# MCU.net
KiCad netlist of a schematic drawn in Altium Designer
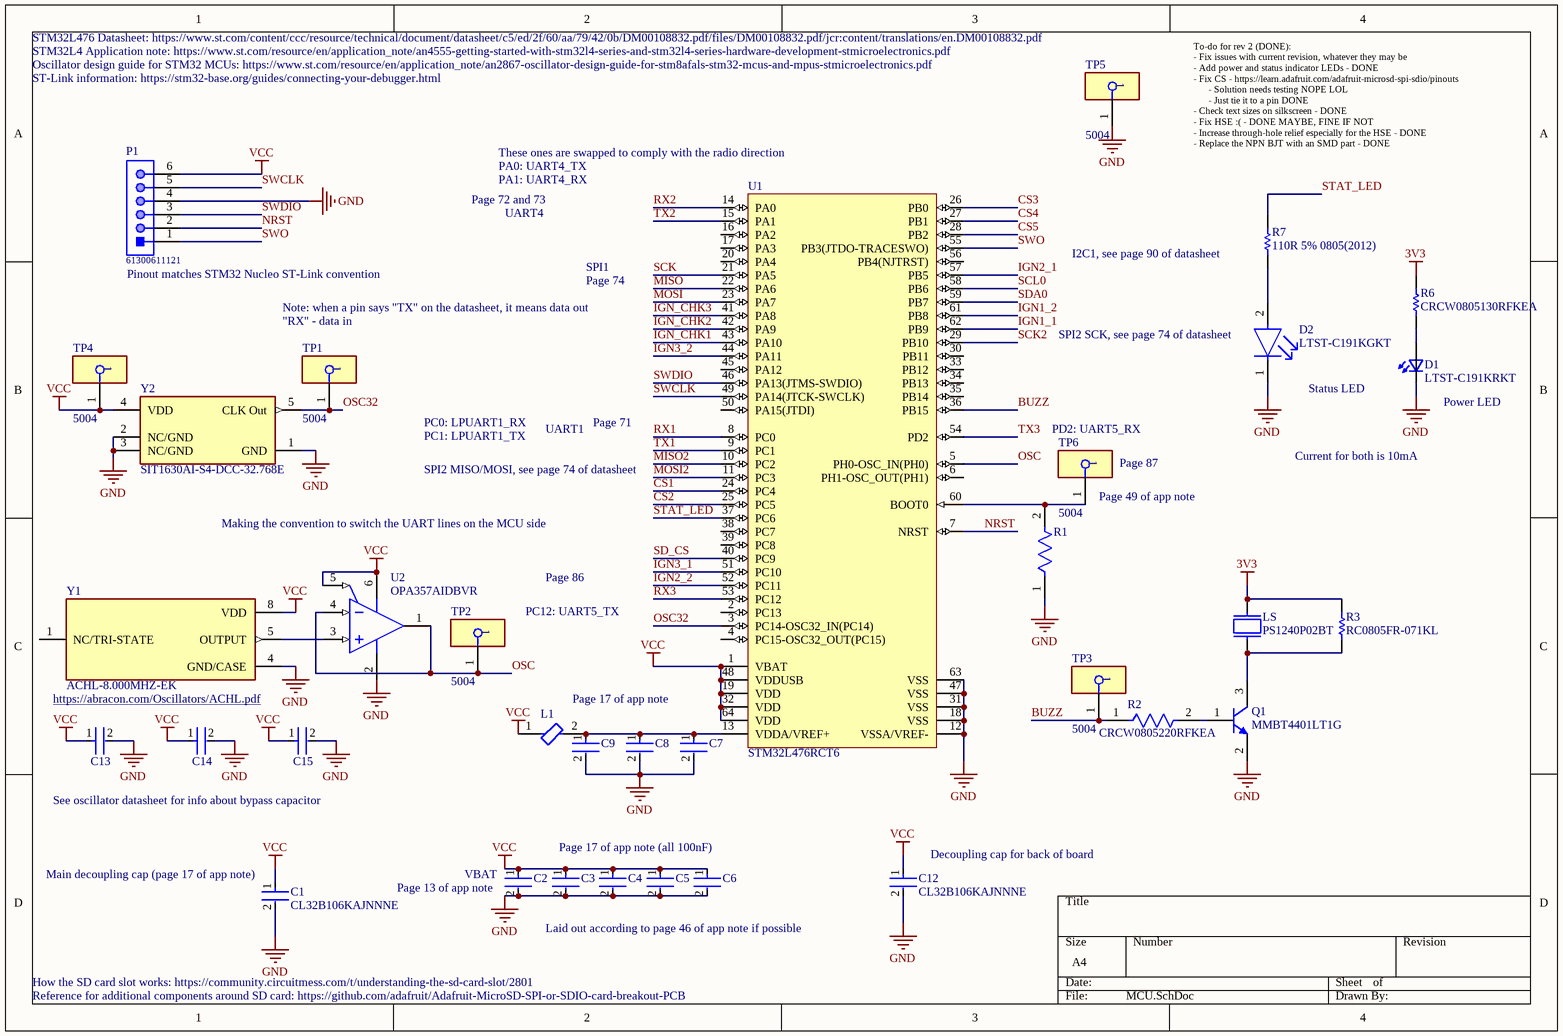
[diagram p0: MCU.SchDoc]

(export (version "E")
  (design (tool "Eeschema 10.0.6"))
  (components
    (comp (ref "C1")
      (value "CL32B106KAJNNNE")
      (footprint "FP-CL32-IPC_B")
      (description "Cap Ceramic 10uF 25V X7R ±10% SMD 1210 +125°C Embossed T/R")
      (fields (field (name "TOLERANCE") "10%") (field (name "VOLTAGE") "25V"))
      (libsource (lib "Altium Content Vault") (part "b4654b650e69147ec39a6b967a45e02"))
    )
    (comp (ref "C2")
      (value "CC0603KRX7R9BB104")
      (footprint "FP-CC0603-DA-MFG")
      (description "CAP CER 0.1UF 50V X7R 0603")
      (fields (field (name "MANUFACTURER") "YAGEO") (field (name "VOLTAGE") "50 V"))
      (libsource (lib "Altium Content Vault") (part "11868f565c42a9108669ba33697ecf6"))
    )
    (comp (ref "C3")
      (value "CC0603KRX7R9BB104")
      (footprint "FP-CC0603-DA-MFG")
      (description "CAP CER 0.1UF 50V X7R 0603")
      (fields (field (name "MANUFACTURER") "YAGEO") (field (name "VOLTAGE") "50 V"))
      (libsource (lib "Altium Content Vault") (part "11868f565c42a9108669ba33697ecf6"))
    )
    (comp (ref "C4")
      (value "CC0603KRX7R9BB104")
      (footprint "FP-CC0603-DA-MFG")
      (description "CAP CER 0.1UF 50V X7R 0603")
      (fields (field (name "MANUFACTURER") "YAGEO") (field (name "VOLTAGE") "50 V"))
      (libsource (lib "Altium Content Vault") (part "11868f565c42a9108669ba33697ecf6"))
    )
    (comp (ref "C5")
      (value "CC0603KRX7R9BB104")
      (footprint "FP-CC0603-DA-MFG")
      (description "CAP CER 0.1UF 50V X7R 0603")
      (fields (field (name "MANUFACTURER") "YAGEO") (field (name "VOLTAGE") "50 V"))
      (libsource (lib "Altium Content Vault") (part "11868f565c42a9108669ba33697ecf6"))
    )
    (comp (ref "C6")
      (value "CC0603KRX7R9BB104")
      (footprint "FP-CC0603-DA-MFG")
      (description "CAP CER 0.1UF 50V X7R 0603")
      (fields (field (name "MANUFACTURER") "YAGEO") (field (name "VOLTAGE") "50 V"))
      (libsource (lib "Altium Content Vault") (part "11868f565c42a9108669ba33697ecf6"))
    )
    (comp (ref "C7")
      (value "CC0603KRX7R9BB104")
      (footprint "FP-CC0603-DA-MFG")
      (description "CAP CER 0.1UF 50V X7R 0603")
      (fields (field (name "MANUFACTURER") "YAGEO") (field (name "VOLTAGE") "50 V"))
      (libsource (lib "Altium Content Vault") (part "11868f565c42a9108669ba33697ecf6"))
    )
    (comp (ref "C8")
      (value "CC0603KRX7R9BB103")
      (footprint "FP-CC0603-DA-MFG")
      (description "CAP CER 10000PF 50V X7R 0603")
      (fields (field (name "TOLERANCE") "0.1") (field (name "MANUFACTURER") "YAGEO"))
      (libsource (lib "Altium Content Vault") (part "11868f565c42a9108669ba33697ecf6"))
    )
    (comp (ref "C9")
      (value "CL10A105KO8NNNC")
      (footprint "FP-CL10-IPC_A")
      (description "Cap Ceramic 1uF 16V X5R ±10% Pad SMD 0603 +85°C T/R")
      (fields (field (name "TOLERANCE") "10%") (field (name "VOLTAGE") "16V"))
      (libsource (lib "Altium Content Vault") (part "b4654b650e69147ec39a6b967a45e02"))
    )
    (comp (ref "C12")
      (value "CL32B106KAJNNNE")
      (footprint "FP-CL32-IPC_B")
      (description "Cap Ceramic 10uF 25V X7R ±10% SMD 1210 +125°C Embossed T/R")
      (fields (field (name "TOLERANCE") "10%") (field (name "VOLTAGE") "25V"))
      (libsource (lib "Altium Content Vault") (part "b4654b650e69147ec39a6b967a45e02"))
    )
    (comp (ref "C13")
      (value "CC0603KRX7R9BB103")
      (footprint "FP-CC0603-DA-MFG")
      (description "CAP CER 10000PF 50V X7R 0603")
      (fields (field (name "TOLERANCE") "0.1") (field (name "MANUFACTURER") "YAGEO"))
      (libsource (lib "Altium Content Vault") (part "11868f565c42a9108669ba33697ecf6"))
    )
    (comp (ref "C14")
      (value "CC0603KRX7R9BB103")
      (footprint "FP-CC0603-DA-MFG")
      (description "CAP CER 10000PF 50V X7R 0603")
      (fields (field (name "TOLERANCE") "0.1") (field (name "MANUFACTURER") "YAGEO"))
      (libsource (lib "Altium Content Vault") (part "11868f565c42a9108669ba33697ecf6"))
    )
    (comp (ref "C15")
      (value "CL10A105KO8NNNC")
      (footprint "FP-CL10-IPC_A")
      (description "Cap Ceramic 1uF 16V X5R ±10% Pad SMD 0603 +85°C T/R")
      (fields (field (name "TOLERANCE") "10%") (field (name "VOLTAGE") "16V"))
      (libsource (lib "Altium Content Vault") (part "b4654b650e69147ec39a6b967a45e02"))
    )
    (comp (ref "D1")
      (value "LTST-C191KRKT")
      (footprint "0603")
      (description "http://octopart.com/ltst-c190krkt-lite-on-549893")
      (fields (field (name "LCSC PART #") "C125099"))
      (libsource (lib "LTST-C191KRKT") (part "LTST-C191KRKT"))
    )
    (comp (ref "D2")
      (value "LTST-C191KGKT")
      (footprint "FP-LTST-C191KGKT-MFG")
      (description "LED GREEN CLEAR SMD")
      (fields (field (name "LCSC PART #") "C125098"))
      (libsource (lib "Altium Content Vault") (part "8706943c75ba83719d021d2fdc84c58"))
    )
    (comp (ref "L1")
      (value "BLM18EG601SN1D")
      (footprint "FP-BLM18-0_15-t0_8-MFG")
      (description "Chip Ferrite Bead, 0603, 600Ω @ 100MHz, 0.35Ω, 25%, 500mA")
      (fields (field (name "TOLERANCE") "25%") (field (name "LCSC PART #") "C20345"))
      (libsource (lib "Altium Content Vault") (part "5f30dd21d616792df468990f7003faa"))
    )
    (comp (ref "LS")
      (value "PS1240P02BT")
      (footprint "XDCR_PS1240P02BT")
      (description "Buzzers Transducer, Externally Driven Piezo 3V 4kHz 60dB @ 3V, 10cm Through Hole PC Pins")
      (fields (field (name "MF") "TDK"))
      (libsource (lib "PS1240P02BT") (part "PS1240P02BT"))
    )
    (comp (ref "P1")
      (value "61300611121")
      (footprint "61300611121")
      (description "THT Vertical Pin Header WR-PHD, Pitch 2.54 mm, Single Row, 6 pins")
      (fields (field (name "MANUFACTURER") "Wurth Elektronik") (field (name "PUBLISHER") "WurthElektronik"))
      (libsource (lib "Altium Content Vault") (part "WE-CN-1P-M-R6"))
    )
    (comp (ref "Q1")
      (value "MMBT4401LT1G")
      (footprint "ONSC-SOT-23-3-318-08_V")
      (description "Switching Transistor, NPN Silicon, 3-Pin SOT-23, Pb-Free, Tape and Reel")
      (fields (field (name "MANUFACTURER") "On Semiconductor") (field (name "LCSC PART #") "C31776"))
      (libsource (lib "Altium Content Vault") (part "ONSC-NPN-B1E2C3-3"))
    )
    (comp (ref "R1")
      (value "AC0805FR-0710KL")
      (footprint "FP-AC0805-MFG")
      (description "RES SMD 10K OHM 1% 1/8W 0805")
      (fields
        (field (name "OCTOPART") "https://octopart.com/ac0805fr-0710kl-yageo-21711112")
        (field (name "MANUFACTURER") "Yageo")
      )
      (libsource (lib "Altium Content Vault") (part "1029c3af85768c4190bb7ad29bc67b5"))
    )
    (comp (ref "R2")
      (value "CRCW0805220RFKEA")
      (footprint "FP-CRCW0805-e3-MFG")
      (description "RES Thick Film, 220Ω, 1%, 0.125W, 100ppm/°C, 0805")
      (fields (field (name "TOLERANCE") "1%") (field (name "LCSC PART #") "C844204"))
      (libsource (lib "Altium Content Vault") (part "1029c3af85768c4190bb7ad29bc67b5"))
    )
    (comp (ref "R3")
      (value "RC0805FR-071KL")
      (footprint "RESC2013X60X35ML10T20")
      (description "Chip Resistor, 1 KOhm, +/- 1%, 125 mW, -55 to 155 degC, 0805 (2012 Metric), RoHS, Tape and Reel")
      (fields (field (name "TOLERANCE") "1%") (field (name "MANUFACTURER") "Yageo"))
      (libsource (lib "Altium Content Vault") (part "RES-2"))
    )
    (comp (ref "R6")
      (value "CRCW0805130RFKEA")
      (footprint "RESC2013X50X30ML20T20")
      (fields (field (name "MANUFACTURER") "Vishay Dale") (field (name "LCSC PART #") "C3151699"))
      (libsource (lib "Altium Content Vault") (part "RES"))
    )
    (comp (ref "R7")
      (value "110R 5% 0805(2012)")
      (footprint "RESC0805(2012)_N")
      (description "110R 0.125W 5% 0805 (2012 Metric)  SMD")
      (fields (field (name "POWER") "0.125 W") (field (name "TOLERANCE") "5 %"))
      (libsource (lib "Altium Content Vault") (part "RES"))
    )
    (comp (ref "TP1")
      (value "5004")
      (footprint "FP-5004-MFG")
      (description "PC TEST POINT MINIATURE YELLOW")
      (fields
        (field (name "MANUFACTURER") "Keystone")
        (field (name "OCTOPART") "https://octopart.com/5004-keystone-28591")
      )
      (libsource (lib "Altium Content Vault") (part "98815daf2f2c152b0c43f5ab9800df6"))
    )
    (comp (ref "TP2")
      (value "5004")
      (footprint "FP-5004-MFG")
      (description "PC TEST POINT MINIATURE YELLOW")
      (fields
        (field (name "MANUFACTURER") "Keystone")
        (field (name "OCTOPART") "https://octopart.com/5004-keystone-28591")
      )
      (libsource (lib "Altium Content Vault") (part "98815daf2f2c152b0c43f5ab9800df6"))
    )
    (comp (ref "TP3")
      (value "5004")
      (footprint "FP-5004-MFG")
      (description "PC TEST POINT MINIATURE YELLOW")
      (fields
        (field (name "MANUFACTURER") "Keystone")
        (field (name "OCTOPART") "https://octopart.com/5004-keystone-28591")
      )
      (libsource (lib "Altium Content Vault") (part "98815daf2f2c152b0c43f5ab9800df6"))
    )
    (comp (ref "TP4")
      (value "5004")
      (footprint "FP-5004-MFG")
      (description "PC TEST POINT MINIATURE YELLOW")
      (fields
        (field (name "MANUFACTURER") "Keystone")
        (field (name "OCTOPART") "https://octopart.com/5004-keystone-28591")
      )
      (libsource (lib "Altium Content Vault") (part "98815daf2f2c152b0c43f5ab9800df6"))
    )
    (comp (ref "TP5")
      (value "5004")
      (footprint "FP-5004-MFG")
      (description "PC TEST POINT MINIATURE YELLOW")
      (fields
        (field (name "MANUFACTURER") "Keystone")
        (field (name "OCTOPART") "https://octopart.com/5004-keystone-28591")
      )
      (libsource (lib "Altium Content Vault") (part "98815daf2f2c152b0c43f5ab9800df6"))
    )
    (comp (ref "TP6")
      (value "5004")
      (footprint "FP-5004-MFG")
      (description "PC TEST POINT MINIATURE YELLOW")
      (fields
        (field (name "MANUFACTURER") "Keystone")
        (field (name "OCTOPART") "https://octopart.com/5004-keystone-28591")
      )
      (libsource (lib "Altium Content Vault") (part "98815daf2f2c152b0c43f5ab9800df6"))
    )
    (comp (ref "U1")
      (value "STM32L476RCT6")
      (footprint "STM-LQFP64_L")
      (fields (field (name "MANUFACTURER") "STMicroelectronics") (field (name "LCSC PART #") "C73245"))
      (libsource (lib "Altium Content Vault") (part "MC-ARM-STM32L4X6-LQFP64"))
    )
    (comp (ref "U2")
      (value "OPA357AIDBVR")
      (footprint "DBV0006A_L")
      (fields (field (name "MANUFACTURER") "Texas Instruments") (field (name "LCSC PART #") "C139385"))
      (libsource (lib "Altium Content Vault") (part "TI-OPA35XDBV6"))
    )
    (comp (ref "Y1")
      (value "ACHL-8.000MHZ-EK")
      (footprint "XTAL_ACHL-8.000MHZ-EK")
      (libsource (lib "ACHL-8.000MHZ-EK") (part "ACHL-8.000MHZ-EK"))
    )
    (comp (ref "Y2")
      (value "SIT1630AI-S4-DCC-32.768E")
      (footprint "FP-SiT1630-S-IPC_A")
      (description "MEMS OSC XO 32.7680KHZ LVCMOS")
      (libsource (lib "Altium Content Vault") (part "93232e8e4595095947db9034d0b3f1e"))
    )
  )
  (nets
    (net (code "1") (name "/BUZZ") (class "Default")
      (node (ref "R2") (pin "1") (pinfunction "1_1") (pintype "passive"))
      (node (ref "TP3") (pin "1") (pinfunction "1_1") (pintype "passive"))
      (node (ref "U1") (pin "36") (pinfunction "PB15_36") (pintype "bidirectional"))
    )
    (net (code "2") (name "/CS1") (class "Default")
      (node (ref "U1") (pin "24") (pinfunction "PC4_24") (pintype "bidirectional"))
    )
    (net (code "3") (name "/CS2") (class "Default")
      (node (ref "U1") (pin "25") (pinfunction "PC5_25") (pintype "bidirectional"))
    )
    (net (code "4") (name "/CS3") (class "Default")
      (node (ref "U1") (pin "26") (pinfunction "PB0_26") (pintype "bidirectional"))
    )
    (net (code "5") (name "/CS4") (class "Default")
      (node (ref "U1") (pin "27") (pinfunction "PB1_27") (pintype "bidirectional"))
    )
    (net (code "6") (name "/CS5") (class "Default")
      (node (ref "U1") (pin "28") (pinfunction "PB2_28") (pintype "bidirectional"))
    )
    (net (code "7") (name "/IGN1_1") (class "Default")
      (node (ref "U1") (pin "62") (pinfunction "PB9_62") (pintype "bidirectional"))
    )
    (net (code "8") (name "/IGN1_2") (class "Default")
      (node (ref "U1") (pin "61") (pinfunction "PB8_61") (pintype "bidirectional"))
    )
    (net (code "9") (name "/IGN2_1") (class "Default")
      (node (ref "U1") (pin "57") (pinfunction "PB5_57") (pintype "bidirectional"))
    )
    (net (code "10") (name "/IGN2_2") (class "Default")
      (node (ref "U1") (pin "52") (pinfunction "PC11_52") (pintype "bidirectional"))
    )
    (net (code "11") (name "/IGN3_1") (class "Default")
      (node (ref "U1") (pin "51") (pinfunction "PC10_51") (pintype "bidirectional"))
    )
    (net (code "12") (name "/IGN3_2") (class "Default")
      (node (ref "U1") (pin "44") (pinfunction "PA11_44") (pintype "bidirectional"))
    )
    (net (code "13") (name "/IGN_CHK1") (class "Default")
      (node (ref "U1") (pin "43") (pinfunction "PA10_43") (pintype "bidirectional"))
    )
    (net (code "14") (name "/IGN_CHK2") (class "Default")
      (node (ref "U1") (pin "42") (pinfunction "PA9_42") (pintype "bidirectional"))
    )
    (net (code "15") (name "/IGN_CHK3") (class "Default")
      (node (ref "U1") (pin "41") (pinfunction "PA8_41") (pintype "bidirectional"))
    )
    (net (code "16") (name "/MISO") (class "Default")
      (node (ref "U1") (pin "22") (pinfunction "PA6_22") (pintype "bidirectional"))
    )
    (net (code "17") (name "/MISO2") (class "Default")
      (node (ref "U1") (pin "10") (pinfunction "PC2_10") (pintype "bidirectional"))
    )
    (net (code "18") (name "/MOSI") (class "Default")
      (node (ref "U1") (pin "23") (pinfunction "PA7_23") (pintype "bidirectional"))
    )
    (net (code "19") (name "/MOSI2") (class "Default")
      (node (ref "U1") (pin "11") (pinfunction "PC3_11") (pintype "bidirectional"))
    )
    (net (code "20") (name "/NRST") (class "Default")
      (node (ref "P1") (pin "2") (pinfunction "2_2") (pintype "passive"))
      (node (ref "U1") (pin "7") (pinfunction "NRST_7") (pintype "bidirectional"))
    )
    (net (code "21") (name "/OSC") (class "Default")
      (node (ref "TP2") (pin "1") (pinfunction "1_1") (pintype "passive"))
      (node (ref "U1") (pin "5") (pinfunction "PH0-OSC_IN(PH0)_5") (pintype "bidirectional"))
      (node (ref "U2") (pin "1") (pinfunction "OUT_1") (pintype "tri_state"))
      (node (ref "U2") (pin "4") (pinfunction "IN-_4") (pintype "input"))
    )
    (net (code "22") (name "/OSC32") (class "Default")
      (node (ref "TP1") (pin "1") (pinfunction "1_1") (pintype "passive"))
      (node (ref "U1") (pin "3") (pinfunction "PC14-OSC32_IN(PC14)_3") (pintype "bidirectional"))
      (node (ref "Y2") (pin "5") (pinfunction "CLK_Out_5") (pintype "output"))
    )
    (net (code "23") (name "/RX1") (class "Default")
      (node (ref "U1") (pin "8") (pinfunction "PC0_8") (pintype "bidirectional"))
    )
    (net (code "24") (name "/RX2") (class "Default")
      (node (ref "U1") (pin "14") (pinfunction "PA0_14") (pintype "bidirectional"))
    )
    (net (code "25") (name "/RX3") (class "Default")
      (node (ref "U1") (pin "53") (pinfunction "PC12_53") (pintype "bidirectional"))
    )
    (net (code "26") (name "/SCK") (class "Default")
      (node (ref "U1") (pin "21") (pinfunction "PA5_21") (pintype "bidirectional"))
    )
    (net (code "27") (name "/SCK2") (class "Default")
      (node (ref "U1") (pin "29") (pinfunction "PB10_29") (pintype "bidirectional"))
    )
    (net (code "28") (name "/SCL0") (class "Default")
      (node (ref "U1") (pin "58") (pinfunction "PB6_58") (pintype "bidirectional"))
    )
    (net (code "29") (name "/SDA0") (class "Default")
      (node (ref "U1") (pin "59") (pinfunction "PB7_59") (pintype "bidirectional"))
    )
    (net (code "30") (name "/SD_CS") (class "Default")
      (node (ref "U1") (pin "40") (pinfunction "PC9_40") (pintype "bidirectional"))
    )
    (net (code "31") (name "/STAT_LED") (class "Default")
      (node (ref "R7") (pin "2") (pinfunction "2_2") (pintype "passive"))
      (node (ref "U1") (pin "37") (pinfunction "PC6_37") (pintype "bidirectional"))
    )
    (net (code "32") (name "/SWCLK") (class "Default")
      (node (ref "P1") (pin "5") (pinfunction "5_5") (pintype "passive"))
      (node (ref "U1") (pin "49") (pinfunction "PA14(JTCK-SWCLK)_49") (pintype "bidirectional"))
    )
    (net (code "33") (name "/SWDIO") (class "Default")
      (node (ref "P1") (pin "3") (pinfunction "3_3") (pintype "passive"))
      (node (ref "U1") (pin "46") (pinfunction "PA13(JTMS-SWDIO)_46") (pintype "bidirectional"))
    )
    (net (code "34") (name "/SWO") (class "Default")
      (node (ref "P1") (pin "1") (pinfunction "1_1") (pintype "passive"))
      (node (ref "U1") (pin "55") (pinfunction "PB3(JTDO-TRACESWO)_55") (pintype "bidirectional"))
    )
    (net (code "35") (name "/TX1") (class "Default")
      (node (ref "U1") (pin "9") (pinfunction "PC1_9") (pintype "bidirectional"))
    )
    (net (code "36") (name "/TX2") (class "Default")
      (node (ref "U1") (pin "15") (pinfunction "PA1_15") (pintype "bidirectional"))
    )
    (net (code "37") (name "/TX3") (class "Default")
      (node (ref "U1") (pin "54") (pinfunction "PD2_54") (pintype "bidirectional"))
    )
    (net (code "38") (name "3V3") (class "Default")
      (node (ref "LS") (pin "2") (pinfunction "2_2") (pintype "passive"))
      (node (ref "R3") (pin "2") (pinfunction "2_2") (pintype "passive"))
      (node (ref "R6") (pin "2") (pinfunction "2_2") (pintype "passive"))
    )
    (net (code "39") (name "GND") (class "Default")
      (node (ref "C1") (pin "2") (pinfunction "2_2") (pintype "passive"))
      (node (ref "C12") (pin "2") (pinfunction "2_2") (pintype "passive"))
      (node (ref "C13") (pin "2") (pinfunction "2_2") (pintype "passive"))
      (node (ref "C14") (pin "2") (pinfunction "2_2") (pintype "passive"))
      (node (ref "C15") (pin "2") (pinfunction "2_2") (pintype "passive"))
      (node (ref "C2") (pin "2") (pinfunction "2_2") (pintype "passive"))
      (node (ref "C3") (pin "2") (pinfunction "2_2") (pintype "passive"))
      (node (ref "C4") (pin "2") (pinfunction "2_2") (pintype "passive"))
      (node (ref "C5") (pin "2") (pinfunction "2_2") (pintype "passive"))
      (node (ref "C6") (pin "2") (pinfunction "2_2") (pintype "passive"))
      (node (ref "C7") (pin "2") (pinfunction "2_2") (pintype "passive"))
      (node (ref "C8") (pin "2") (pinfunction "2_2") (pintype "passive"))
      (node (ref "C9") (pin "2") (pinfunction "2_2") (pintype "passive"))
      (node (ref "D1") (pin "1") (pinfunction "K2_1") (pintype "passive"))
      (node (ref "D2") (pin "1") (pinfunction "C_1") (pintype "passive"))
      (node (ref "P1") (pin "4") (pinfunction "4_4") (pintype "passive"))
      (node (ref "Q1") (pin "2") (pinfunction "E_2") (pintype "passive"))
      (node (ref "R1") (pin "1") (pinfunction "1_1") (pintype "passive"))
      (node (ref "TP5") (pin "1") (pinfunction "1_1") (pintype "passive"))
      (node (ref "U1") (pin "12") (pinfunction "VSSA/VREF-_12") (pintype "power_in"))
      (node (ref "U1") (pin "18") (pinfunction "VSS_18") (pintype "power_in"))
      (node (ref "U1") (pin "31") (pinfunction "VSS_31") (pintype "power_in"))
      (node (ref "U1") (pin "47") (pinfunction "VSS_47") (pintype "power_in"))
      (node (ref "U1") (pin "63") (pinfunction "VSS_63") (pintype "power_in"))
      (node (ref "U2") (pin "2") (pinfunction "V-_2") (pintype "power_in"))
      (node (ref "Y1") (pin "4") (pinfunction "GND/CASE_4") (pintype "passive"))
      (node (ref "Y2") (pin "1") (pinfunction "GND_1") (pintype "power_in"))
      (node (ref "Y2") (pin "2") (pinfunction "NC/GND_2") (pintype "power_in"))
      (node (ref "Y2") (pin "3") (pinfunction "NC/GND_3") (pintype "power_in"))
    )
    (net (code "40") (name "Net-(D1-A2)") (class "Default")
      (node (ref "D1") (pin "2") (pinfunction "A2_2") (pintype "passive"))
      (node (ref "R6") (pin "1") (pinfunction "1_1") (pintype "passive"))
    )
    (net (code "41") (name "Net-(D2-A)") (class "Default")
      (node (ref "D2") (pin "2") (pinfunction "A_2") (pintype "passive"))
      (node (ref "R7") (pin "1") (pinfunction "1_1") (pintype "passive"))
    )
    (net (code "42") (name "Net-(Q1-B)") (class "Default")
      (node (ref "Q1") (pin "1") (pinfunction "B_1") (pintype "passive"))
      (node (ref "R2") (pin "2") (pinfunction "2_2") (pintype "passive"))
    )
    (net (code "43") (name "Net-(Q1-C)") (class "Default")
      (node (ref "LS") (pin "1") (pinfunction "1_1") (pintype "passive"))
      (node (ref "Q1") (pin "3") (pinfunction "C_3") (pintype "passive"))
      (node (ref "R3") (pin "1") (pinfunction "1_1") (pintype "passive"))
    )
    (net (code "44") (name "Net-(U1-BOOT0)") (class "Default")
      (node (ref "R1") (pin "2") (pinfunction "2_2") (pintype "passive"))
      (node (ref "TP6") (pin "1") (pinfunction "1_1") (pintype "passive"))
      (node (ref "U1") (pin "60") (pinfunction "BOOT0_60") (pintype "input"))
    )
    (net (code "45") (name "Net-(U1-VDDA{slash}VREF+)") (class "Default")
      (node (ref "C7") (pin "1") (pinfunction "1_1") (pintype "passive"))
      (node (ref "C8") (pin "1") (pinfunction "1_1") (pintype "passive"))
      (node (ref "C9") (pin "1") (pinfunction "1_1") (pintype "passive"))
      (node (ref "L1") (pin "2") (pinfunction "2_2") (pintype "passive"))
      (node (ref "U1") (pin "13") (pinfunction "VDDA/VREF+_13") (pintype "power_in"))
    )
    (net (code "46") (name "Net-(U2-IN+)") (class "Default")
      (node (ref "U2") (pin "3") (pinfunction "IN+_3") (pintype "input"))
      (node (ref "Y1") (pin "5") (pinfunction "OUTPUT_5") (pintype "output"))
    )
    (net (code "47") (name "VCC") (class "Default")
      (node (ref "C1") (pin "1") (pinfunction "1_1") (pintype "passive"))
      (node (ref "C12") (pin "1") (pinfunction "1_1") (pintype "passive"))
      (node (ref "C13") (pin "1") (pinfunction "1_1") (pintype "passive"))
      (node (ref "C14") (pin "1") (pinfunction "1_1") (pintype "passive"))
      (node (ref "C15") (pin "1") (pinfunction "1_1") (pintype "passive"))
      (node (ref "C2") (pin "1") (pinfunction "1_1") (pintype "passive"))
      (node (ref "C3") (pin "1") (pinfunction "1_1") (pintype "passive"))
      (node (ref "C4") (pin "1") (pinfunction "1_1") (pintype "passive"))
      (node (ref "C5") (pin "1") (pinfunction "1_1") (pintype "passive"))
      (node (ref "C6") (pin "1") (pinfunction "1_1") (pintype "passive"))
      (node (ref "L1") (pin "1") (pinfunction "1_1") (pintype "passive"))
      (node (ref "P1") (pin "6") (pinfunction "6_6") (pintype "passive"))
      (node (ref "TP4") (pin "1") (pinfunction "1_1") (pintype "passive"))
      (node (ref "U1") (pin "1") (pinfunction "VBAT_1") (pintype "power_in"))
      (node (ref "U1") (pin "19") (pinfunction "VDD_19") (pintype "power_in"))
      (node (ref "U1") (pin "32") (pinfunction "VDD_32") (pintype "power_in"))
      (node (ref "U1") (pin "48") (pinfunction "VDDUSB_48") (pintype "power_in"))
      (node (ref "U1") (pin "64") (pinfunction "VDD_64") (pintype "power_in"))
      (node (ref "U2") (pin "5") (pinfunction "ENABLE_5") (pintype "input"))
      (node (ref "U2") (pin "6") (pinfunction "V+_6") (pintype "power_in"))
      (node (ref "Y1") (pin "8") (pinfunction "VDD_8") (pintype "power_in"))
      (node (ref "Y2") (pin "4") (pinfunction "VDD_4") (pintype "power_in"))
    )
    (net (code "48") (name "unconnected-(U1-PA2-Pad16)") (class "Default")
      (node (ref "U1") (pin "16") (pinfunction "PA2_16") (pintype "bidirectional"))
    )
    (net (code "49") (name "unconnected-(U1-PA3-Pad17)") (class "Default")
      (node (ref "U1") (pin "17") (pinfunction "PA3_17") (pintype "bidirectional"))
    )
    (net (code "50") (name "unconnected-(U1-PA4-Pad20)") (class "Default")
      (node (ref "U1") (pin "20") (pinfunction "PA4_20") (pintype "bidirectional"))
    )
    (net (code "51") (name "unconnected-(U1-PA12-Pad45)") (class "Default")
      (node (ref "U1") (pin "45") (pinfunction "PA12_45") (pintype "bidirectional"))
    )
    (net (code "52") (name "unconnected-(U1-PA15(JTDI)-Pad50)") (class "Default")
      (node (ref "U1") (pin "50") (pinfunction "PA15(JTDI)_50") (pintype "bidirectional"))
    )
    (net (code "53") (name "unconnected-(U1-PB4(NJTRST)-Pad56)") (class "Default")
      (node (ref "U1") (pin "56") (pinfunction "PB4(NJTRST)_56") (pintype "bidirectional"))
    )
    (net (code "54") (name "unconnected-(U1-PB11-Pad30)") (class "Default")
      (node (ref "U1") (pin "30") (pinfunction "PB11_30") (pintype "bidirectional"))
    )
    (net (code "55") (name "unconnected-(U1-PB12-Pad33)") (class "Default")
      (node (ref "U1") (pin "33") (pinfunction "PB12_33") (pintype "bidirectional"))
    )
    (net (code "56") (name "unconnected-(U1-PB13-Pad34)") (class "Default")
      (node (ref "U1") (pin "34") (pinfunction "PB13_34") (pintype "bidirectional"))
    )
    (net (code "57") (name "unconnected-(U1-PB14-Pad35)") (class "Default")
      (node (ref "U1") (pin "35") (pinfunction "PB14_35") (pintype "bidirectional"))
    )
    (net (code "58") (name "unconnected-(U1-PC7-Pad38)") (class "Default")
      (node (ref "U1") (pin "38") (pinfunction "PC7_38") (pintype "bidirectional"))
    )
    (net (code "59") (name "unconnected-(U1-PC8-Pad39)") (class "Default")
      (node (ref "U1") (pin "39") (pinfunction "PC8_39") (pintype "bidirectional"))
    )
    (net (code "60") (name "unconnected-(U1-PC13-Pad2)") (class "Default")
      (node (ref "U1") (pin "2") (pinfunction "PC13_2") (pintype "bidirectional"))
    )
    (net (code "61") (name "unconnected-(U1-PC15-OSC32_OUT(PC15)-Pad4)") (class "Default")
      (node (ref "U1") (pin "4") (pinfunction "PC15-OSC32_OUT(PC15)_4") (pintype "bidirectional"))
    )
    (net (code "62") (name "unconnected-(U1-PH1-OSC_OUT(PH1)-Pad6)") (class "Default")
      (node (ref "U1") (pin "6") (pinfunction "PH1-OSC_OUT(PH1)_6") (pintype "bidirectional"))
    )
    (net (code "63") (name "unconnected-(Y1-NC{slash}TRI-STATE-Pad1)") (class "Default")
      (node (ref "Y1") (pin "1") (pinfunction "NC/TRI-STATE_1") (pintype "passive"))
    )
  )
)
